# Gas_Sampler-BME_280.net
KiCad netlist of a schematic drawn in Altium Designer
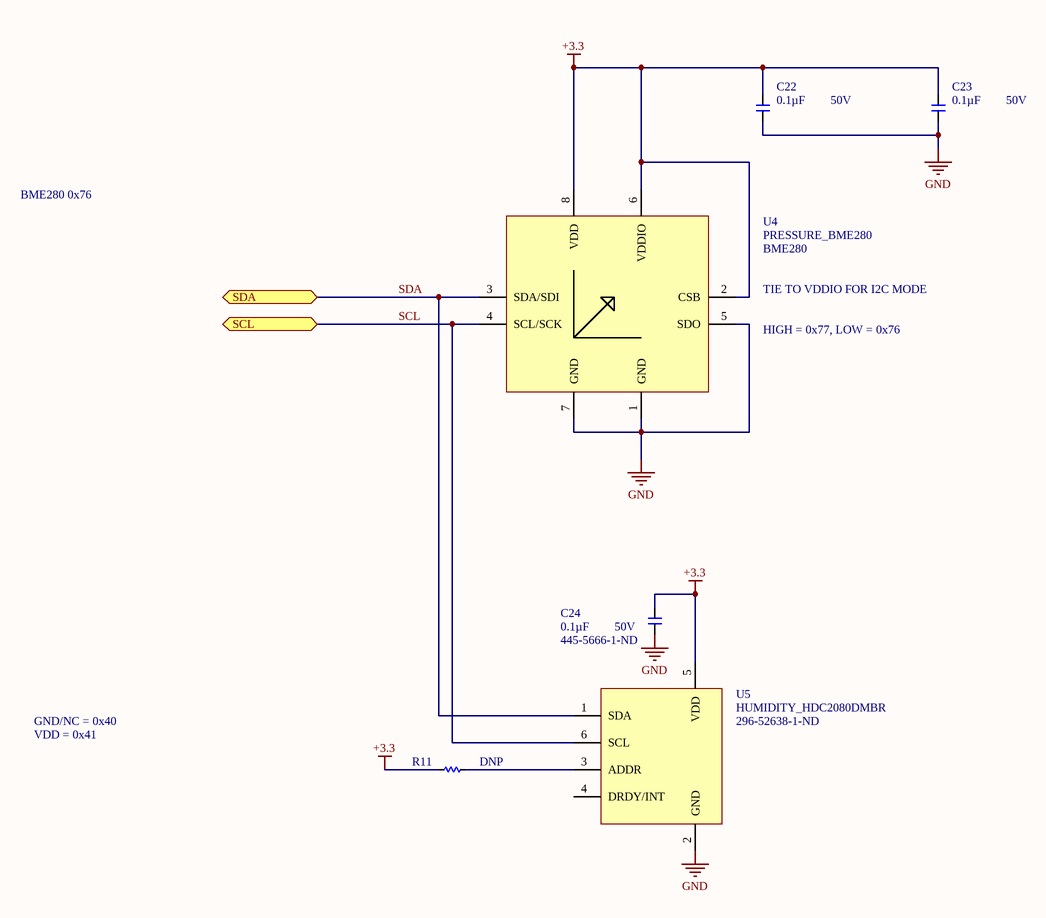
[diagram p0: Gas_Sampler-BME_280.SchDoc]

(export (version "E")
  (design (tool "Eeschema 10.0.6"))
  (components
    (comp (ref "C22")
      (value "0.1µF")
      (footprint "C0603")
      (description "CAP CER 0.1UF 50V 10% X7R 0603")
      (fields
        (field (name "MANUFACTURER") "TDK Corporation")
        (field (name "MANUFACTURER PART NUMBER") "CGA3E2X7R1H104K080AA")
        (field (name "VOLTAGE - RATED") "50V")
      )
      (libsource (lib "capacitor") (part "CAP_CER_0603_0.1UF_50V_10%_X7R"))
    )
    (comp (ref "C23")
      (value "0.1µF")
      (footprint "C0603")
      (description "CAP CER 0.1UF 50V 10% X7R 0603")
      (fields
        (field (name "MANUFACTURER") "TDK Corporation")
        (field (name "MANUFACTURER PART NUMBER") "CGA3E2X7R1H104K080AA")
        (field (name "VOLTAGE - RATED") "50V")
      )
      (libsource (lib "capacitor") (part "CAP_CER_0603_0.1UF_50V_10%_X7R"))
    )
    (comp (ref "C24")
      (value "0.1µF")
      (footprint "C0603")
      (description "CAP CER 0.1UF 50V 10% X7R 0603")
      (fields
        (field (name "MANUFACTURER") "TDK Corporation")
        (field (name "MANUFACTURER PART NUMBER") "CGA3E2X7R1H104K080AA")
        (field (name "VOLTAGE - RATED") "50V")
        (field (name "SUPPLIER PART NUMBER 1") "445-5666-1-ND")
      )
      (libsource (lib "capacitor") (part "CAP_CER_0603_0.1UF_50V_10%_X7R"))
    )
    (comp (ref "R11")
      (value "DNP")
      (footprint "R0603")
      (description "RES DNP 0603 SMD")
      (fields (field (name "PART NUMBER") "000-00000-00") (field (name "Comment") "RES_0603_DNP"))
      (libsource (lib "resistor") (part "RES_0603_DNP"))
    )
    (comp (ref "U4")
      (value "PRESSURE_BME280")
      (footprint "BOSCH_BME280")
      (description "SENSOR PRESSURE HUMIDITY TEMP")
      (fields
        (field (name "MANUFACTURER") "Bosch Sensortec")
        (field (name "MANUFACTURER PART NUMBER") "BME280")
      )
      (libsource (lib "sensor") (part "PRESSURE_BME280"))
    )
    (comp (ref "U5")
      (value "HUMIDITY_HDC2080DMBR")
      (footprint "6DFN3X3_NO_EP")
      (description "Humidity Temperature Sensor 0 ~ 100% RH I²C ±2% RH Surface Mount")
      (fields
        (field (name "MANUFACTURER") "Texas Instruments")
        (field (name "MANUFACTURER PART NUMBER") "HDC2080DMBR")
        (field (name "SUPPLIER PART NUMBER 1") "296-52638-1-ND")
      )
      (libsource (lib "sensor") (part "HUMIDITY_HDC2080DMBR"))
    )
  )
  (nets
    (net (code "1") (name "+3.3") (class "Default")
      (node (ref "C22") (pin "1") (pintype "passive"))
      (node (ref "C23") (pin "1") (pintype "passive"))
      (node (ref "C24") (pin "1") (pintype "passive"))
      (node (ref "R11") (pin "1") (pintype "passive"))
      (node (ref "U4") (pin "2") (pinfunction "CSB_2") (pintype "passive"))
      (node (ref "U4") (pin "6") (pinfunction "VDDIO_6") (pintype "passive"))
      (node (ref "U4") (pin "8") (pinfunction "VDD_8") (pintype "passive"))
      (node (ref "U5") (pin "5") (pinfunction "VDD_5") (pintype "passive"))
    )
    (net (code "2") (name "/SCL") (class "Default")
      (node (ref "U4") (pin "4") (pinfunction "SCL/SCK_4") (pintype "passive"))
      (node (ref "U5") (pin "6") (pinfunction "SCL_6") (pintype "passive"))
    )
    (net (code "3") (name "/SDA") (class "Default")
      (node (ref "U4") (pin "3") (pinfunction "SDA/SDI_3") (pintype "passive"))
      (node (ref "U5") (pin "1") (pinfunction "SDA_1") (pintype "passive"))
    )
    (net (code "4") (name "GND") (class "Default")
      (node (ref "C22") (pin "2") (pintype "passive"))
      (node (ref "C23") (pin "2") (pintype "passive"))
      (node (ref "C24") (pin "2") (pintype "passive"))
      (node (ref "U4") (pin "1") (pinfunction "GND_1") (pintype "passive"))
      (node (ref "U4") (pin "5") (pinfunction "SDO_5") (pintype "passive"))
      (node (ref "U4") (pin "7") (pinfunction "GND_7") (pintype "passive"))
      (node (ref "U5") (pin "2") (pinfunction "GND_2") (pintype "passive"))
    )
    (net (code "5") (name "Net-(U5-ADDR)") (class "Default")
      (node (ref "R11") (pin "2") (pintype "passive"))
      (node (ref "U5") (pin "3") (pinfunction "ADDR_3") (pintype "passive"))
    )
    (net (code "6") (name "unconnected-(U5-DRDY{slash}INT-Pad4)") (class "Default")
      (node (ref "U5") (pin "4") (pinfunction "DRDY/INT_4") (pintype "passive"))
    )
  )
)
